# Walrus_Power.net
KiCad netlist of a schematic drawn in Altium Designer
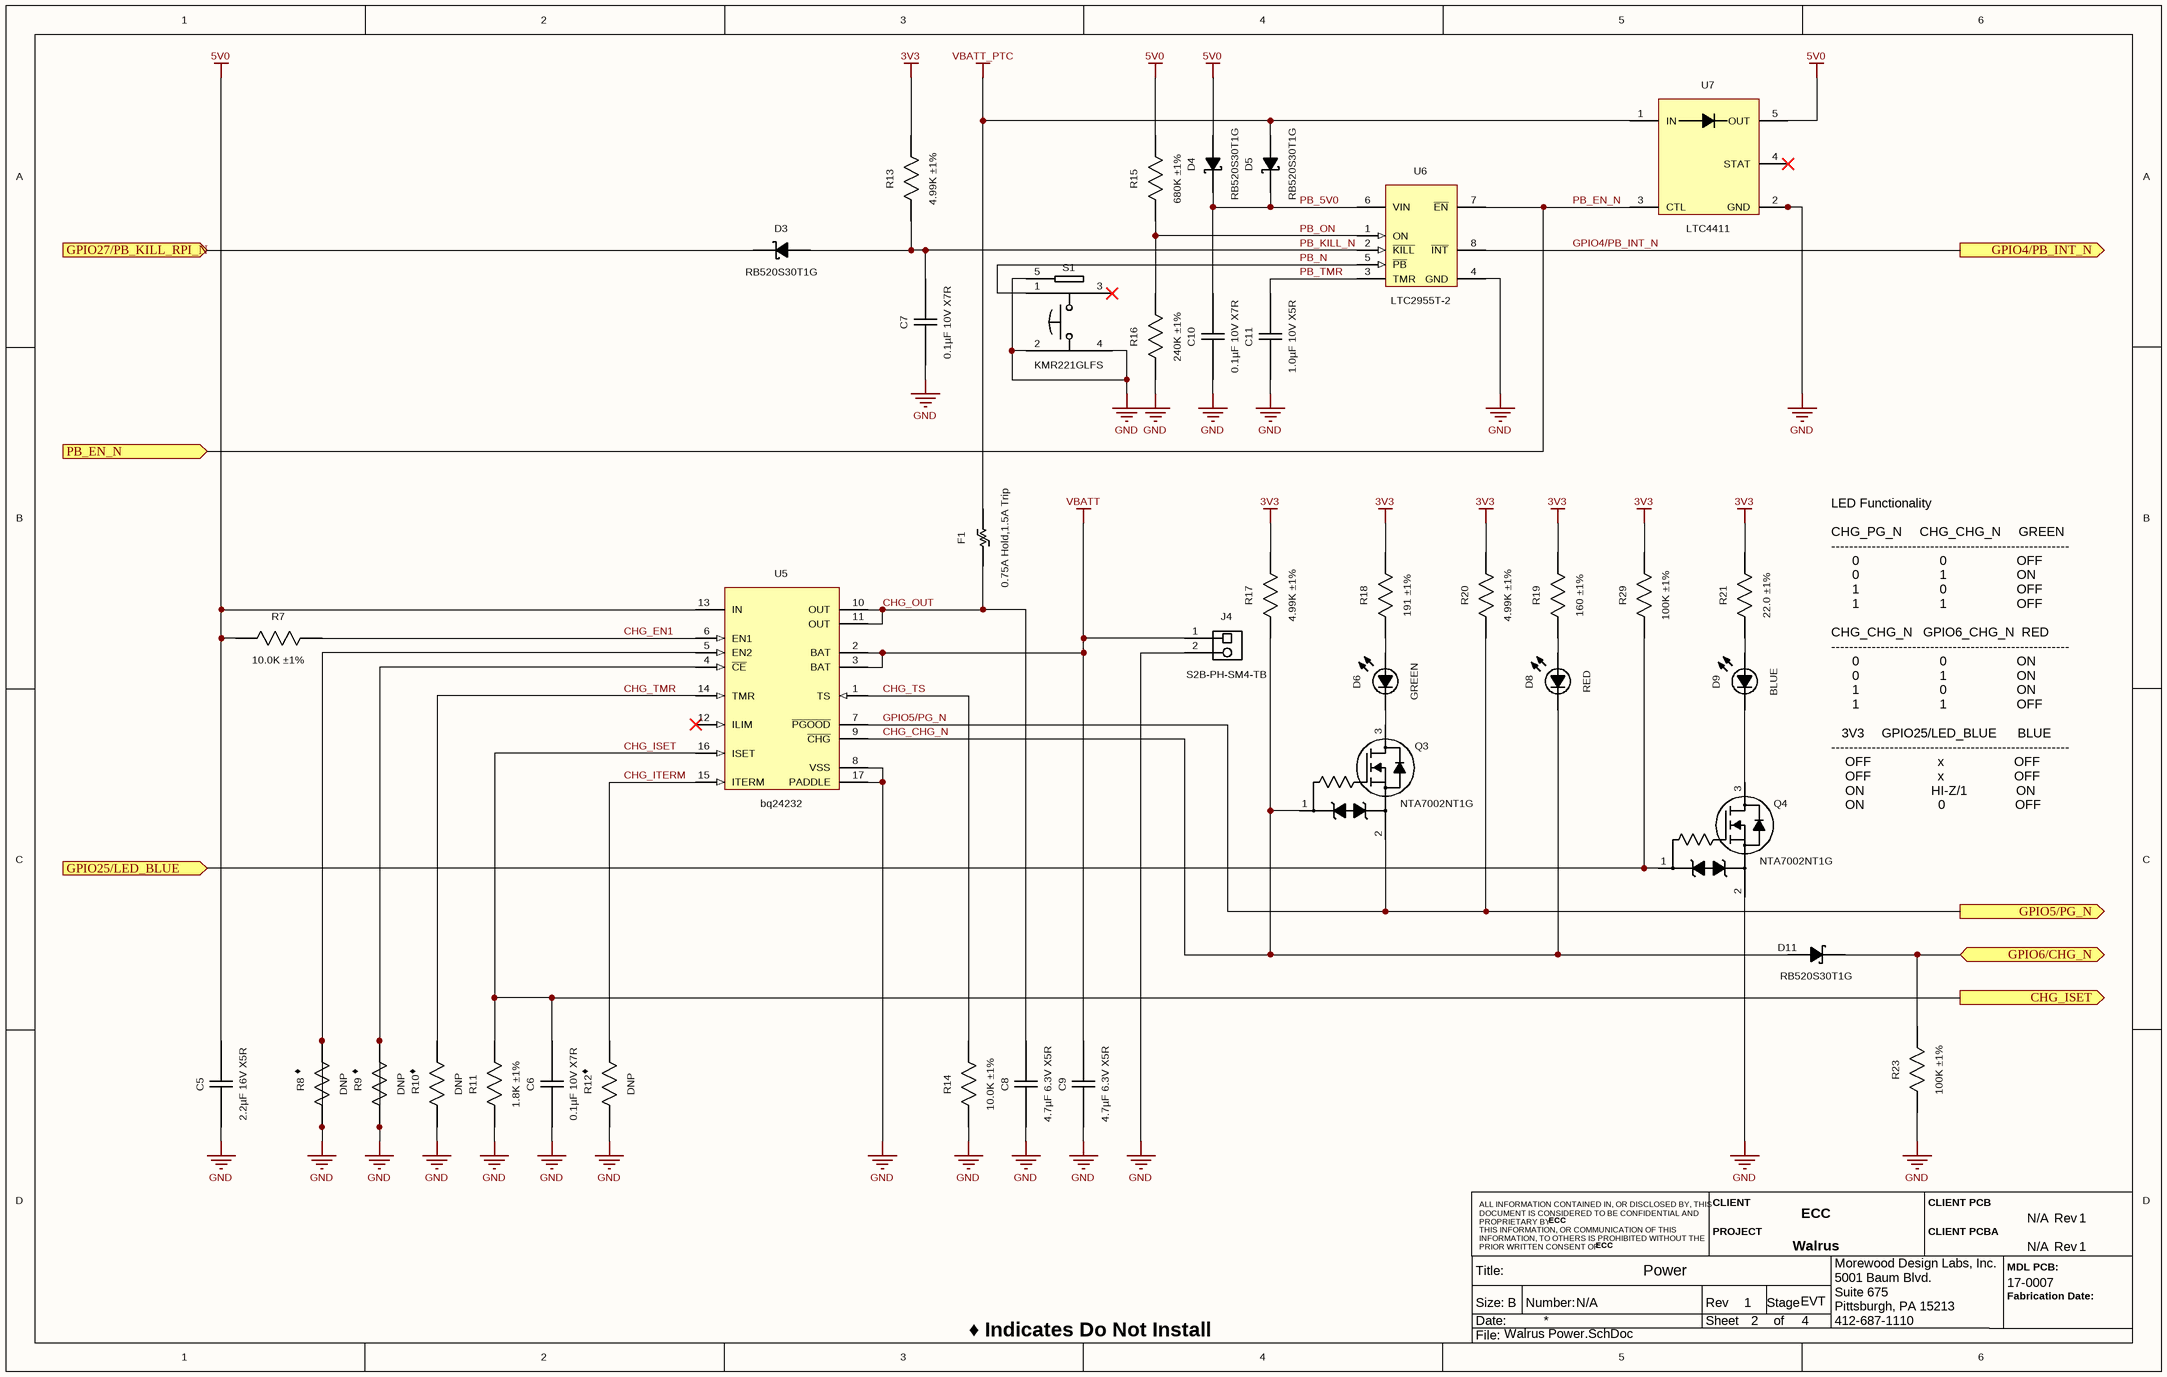
[diagram p0: Walrus Power.SchDoc]

(export (version "E")
  (design (tool "Eeschema 10.0.6"))
  (components
    (comp (ref "C5")
      (value "2.2µF 16V X5R")
      (footprint "CAPC1005X60L(0402)")
      (description "Ceramic Chip Capacitor")
      (fields
        (field (name "MDLPARTNUMBER") "CAP_000166")
        (field (name "TOLERANCE") "±10%")
        (field (name "CREATOR") "R. Casciola")
      )
      (libsource (lib "Morewood Labs") (part "Capacitor 1"))
    )
    (comp (ref "C6")
      (value "0.1µF 10V X7R")
      (footprint "CAPC1005X60L(0402_FLEXTRONICS)")
      (description "Ceramic Chip Capacitor")
      (fields
        (field (name "MDLPARTNUMBER") "CAP_000208")
        (field (name "TOLERANCE") "±10%")
        (field (name "CREATOR") "R. Casciola")
      )
      (libsource (lib "Morewood Labs") (part "Capacitor 1"))
    )
    (comp (ref "C7")
      (value "0.1µF 10V X7R")
      (footprint "CAPC1005X60L(0402_FLEXTRONICS)")
      (description "Ceramic Chip Capacitor")
      (fields
        (field (name "MDLPARTNUMBER") "CAP_000208")
        (field (name "TOLERANCE") "±10%")
        (field (name "CREATOR") "R. Casciola")
      )
      (libsource (lib "Morewood Labs") (part "Capacitor 1"))
    )
    (comp (ref "C8")
      (value "4.7µF 6.3V X5R")
      (footprint "CAPC1005X60L(0402)")
      (description "Ceramic Chip Capacitor")
      (fields
        (field (name "MDLPARTNUMBER") "CAP_000063")
        (field (name "TOLERANCE") "±20%")
        (field (name "CREATOR") "R. Casciola")
      )
      (libsource (lib "Morewood Labs") (part "Capacitor 1"))
    )
    (comp (ref "C9")
      (value "4.7µF 6.3V X5R")
      (footprint "CAPC1005X60L(0402)")
      (description "Ceramic Chip Capacitor")
      (fields
        (field (name "MDLPARTNUMBER") "CAP_000063")
        (field (name "TOLERANCE") "±20%")
        (field (name "CREATOR") "R. Casciola")
      )
      (libsource (lib "Morewood Labs") (part "Capacitor 1"))
    )
    (comp (ref "C10")
      (value "0.1µF 10V X7R")
      (footprint "CAPC1005X60L(0402_FLEXTRONICS)")
      (description "Ceramic Chip Capacitor")
      (fields
        (field (name "MDLPARTNUMBER") "CAP_000208")
        (field (name "TOLERANCE") "±10%")
        (field (name "CREATOR") "R. Casciola")
      )
      (libsource (lib "Morewood Labs") (part "Capacitor 1"))
    )
    (comp (ref "C11")
      (value "1.0µF 10V X5R")
      (footprint "CAPC1005X60L(0402_FLEXTRONICS)")
      (description "Ceramic Chip Capacitor")
      (fields
        (field (name "MDLPARTNUMBER") "CAP_000094")
        (field (name "TOLERANCE") "±10%")
        (field (name "CREATOR") "R. Casciola")
      )
      (libsource (lib "Morewood Labs") (part "Capacitor 1"))
    )
    (comp (ref "D3")
      (value "RB520S30T1G")
      (footprint "SODFL1608X70L(SOD-523)")
      (description "Schottky Barrier Diode")
      (fields (field (name "MDLPARTNUMBER") "DIOD_000001") (field (name "CREATOR") "R. Casciola"))
      (libsource (lib "Morewood Labs") (part "Diode 3"))
    )
    (comp (ref "D4")
      (value "RB520S30T1G")
      (footprint "SODFL1608X70L(SOD-523)")
      (description "Schottky Barrier Diode")
      (fields (field (name "MDLPARTNUMBER") "DIOD_000001") (field (name "CREATOR") "R. Casciola"))
      (libsource (lib "Morewood Labs") (part "Diode 3"))
    )
    (comp (ref "D5")
      (value "RB520S30T1G")
      (footprint "SODFL1608X70L(SOD-523)")
      (description "Schottky Barrier Diode")
      (fields (field (name "MDLPARTNUMBER") "DIOD_000001") (field (name "CREATOR") "R. Casciola"))
      (libsource (lib "Morewood Labs") (part "Diode 3"))
    )
    (comp (ref "D6")
      (value "GREEN")
      (footprint "DIOC1608X90L(0603)_GREEN")
      (description "Surface Mounting Chip LED")
      (fields
        (field (name "MDLPARTNUMBER") "DIOD_000061")
        (field (name "MFG1PARTNUMBER") "LTST-C190KGKT")
        (field (name "CREATOR") "R. Casciola")
      )
      (libsource (lib "Morewood Labs") (part "Diode 5"))
    )
    (comp (ref "D8")
      (value "RED")
      (footprint "DIOC1608X90L(0603)_RED")
      (description "Surface Mounting Chip LED")
      (fields
        (field (name "MDLPARTNUMBER") "DIOD_000068")
        (field (name "MFG1PARTNUMBER") "LTST-C190CKT")
        (field (name "CREATOR") "R. Casciola")
      )
      (libsource (lib "Morewood Labs") (part "Diode 5"))
    )
    (comp (ref "D9")
      (value "BLUE")
      (footprint "DIOC1608X90L(0603)_BLUE")
      (description "Surface Mounting Chip LED")
      (fields
        (field (name "MDLPARTNUMBER") "DIOD_000059")
        (field (name "MFG1PARTNUMBER") "LTST-C190TBKT")
        (field (name "CREATOR") "R. Casciola")
      )
      (libsource (lib "Morewood Labs") (part "Diode 5"))
    )
    (comp (ref "D11")
      (value "RB520S30T1G")
      (footprint "SODFL1608X70L(SOD-523)")
      (description "Schottky Barrier Diode")
      (fields (field (name "MDLPARTNUMBER") "DIOD_000001") (field (name "CREATOR") "R. Casciola"))
      (libsource (lib "Morewood Labs") (part "Diode 3"))
    )
    (comp (ref "F1")
      (value "0.75A Hold,1.5A Trip")
      (footprint "FUSC1608X60N(0603)")
      (description "POLY-FUSE® Resettable PTC, Surface Mount > LoRho Series")
      (fields
        (field (name "MDLPARTNUMBER") "FUSE_000007")
        (field (name "MFG1PARTNUMBER") "0603L075SLYR")
        (field (name "CREATOR") "R. Casciola")
      )
      (libsource (lib "Morewood Labs") (part "PPTC 1"))
    )
    (comp (ref "J4")
      (value "S2B-PH-SM4-TB")
      (footprint "JST_S2B-PH-SM4-TB")
      (description "PH CONNECTOR/2.0MM Pitch Side Entry")
      (fields
        (field (name "MDLPARTNUMBER") "CONN_000190")
        (field (name "MFG1PARTNUMBER") "S2B-PH-SM4-TB,S2B-PH-SM4-TB(LF)(SN)")
        (field (name "CREATOR") "R. Casciola")
        (field (name "MODIFER") "R. Casciola")
      )
      (libsource (lib "Morewood Labs") (part "MHDR1X2"))
    )
    (comp (ref "Q3")
      (value "NTA7002NT1G")
      (footprint "SOT50P160X90-3L(SOT416, SC75)")
      (description "Small Signal MOSFET")
      (fields
        (field (name "MDLPARTNUMBER") "TRAN_000002")
        (field (name "CREATOR") "R. Casciola")
        (field (name "MODIFER") "R. Casciola")
      )
      (libsource (lib "Morewood Labs") (part "MOSFET 2"))
    )
    (comp (ref "Q4")
      (value "NTA7002NT1G")
      (footprint "SOT50P160X90-3L(SOT416, SC75)")
      (description "Small Signal MOSFET")
      (fields
        (field (name "MDLPARTNUMBER") "TRAN_000002")
        (field (name "CREATOR") "R. Casciola")
        (field (name "MODIFER") "R. Casciola")
      )
      (libsource (lib "Morewood Labs") (part "MOSFET 2"))
    )
    (comp (ref "R7")
      (value "10.0K ±1%")
      (footprint "RESC1005X40L(0402)")
      (description "Chip Resistor, Thick Film")
      (fields
        (field (name "MDLPARTNUMBER") "RES_000005")
        (field (name "TOLERANCE") "±1%")
        (field (name "CREATOR") "R. Casciola")
      )
      (libsource (lib "Morewood Labs") (part "Resistor 1"))
    )
    (comp (ref "R8")
      (value "DNP")
      (footprint "RESC1005X40L(0402)_DNP")
      (description "Chip Resistor, Thick Film")
      (fields
        (field (name "DNI") "♦")
        (field (name "MDLPARTNUMBER") "RES_000064")
        (field (name "CREATOR") "R. Casciola")
      )
      (libsource (lib "Morewood Labs") (part "Resistor 2"))
    )
    (comp (ref "R9")
      (value "DNP")
      (footprint "RESC1005X40L(0402)_DNP")
      (description "Chip Resistor, Thick Film")
      (fields
        (field (name "DNI") "♦")
        (field (name "MDLPARTNUMBER") "RES_000064")
        (field (name "CREATOR") "R. Casciola")
      )
      (libsource (lib "Morewood Labs") (part "Resistor 2"))
    )
    (comp (ref "R10")
      (value "DNP")
      (footprint "RESC1005X40L(0402)_DNP")
      (description "Chip Resistor, Thick Film")
      (fields
        (field (name "DNI") "♦")
        (field (name "MDLPARTNUMBER") "RES_000064")
        (field (name "CREATOR") "R. Casciola")
      )
      (libsource (lib "Morewood Labs") (part "Resistor 2"))
    )
    (comp (ref "R11")
      (value "1.8K ±1%")
      (footprint "RESC1005X40L(0402)")
      (description "Chip Resistor, Thick Film")
      (fields
        (field (name "MDLPARTNUMBER") "RES_000288")
        (field (name "TOLERANCE") "±1%")
        (field (name "CREATOR") "R. Casciola")
      )
      (libsource (lib "Morewood Labs") (part "Resistor 1"))
    )
    (comp (ref "R12")
      (value "DNP")
      (footprint "RESC1005X40L(0402)_DNP")
      (description "Chip Resistor, Thick Film")
      (fields
        (field (name "DNI") "♦")
        (field (name "MDLPARTNUMBER") "RES_000064")
        (field (name "CREATOR") "R. Casciola")
      )
      (libsource (lib "Morewood Labs") (part "Resistor 2"))
    )
    (comp (ref "R13")
      (value "4.99K ±1%")
      (footprint "RESC1005X40L(0402)")
      (description "Chip Resistor, Thick Film")
      (fields
        (field (name "MDLPARTNUMBER") "RES_000003")
        (field (name "TOLERANCE") "±1%")
        (field (name "CREATOR") "R. Casciola")
      )
      (libsource (lib "Morewood Labs") (part "Resistor 1"))
    )
    (comp (ref "R14")
      (value "10.0K ±1%")
      (footprint "RESC1005X40L(0402)")
      (description "Chip Resistor, Thick Film")
      (fields
        (field (name "MDLPARTNUMBER") "RES_000005")
        (field (name "TOLERANCE") "±1%")
        (field (name "CREATOR") "R. Casciola")
      )
      (libsource (lib "Morewood Labs") (part "Resistor 1"))
    )
    (comp (ref "R15")
      (value "680K ±1%")
      (footprint "RESC1005X40L(0402)")
      (description "Chip Resistor, Thick Film")
      (fields
        (field (name "MDLPARTNUMBER") "RES_000103")
        (field (name "TOLERANCE") "±1%")
        (field (name "CREATOR") "R. Casciola")
      )
      (libsource (lib "Morewood Labs") (part "Resistor 1"))
    )
    (comp (ref "R16")
      (value "240K ±1%")
      (footprint "RESC1005X40L(0402)")
      (description "Chip Resistor, Thick Film")
      (fields
        (field (name "MDLPARTNUMBER") "RES_000165")
        (field (name "TOLERANCE") "±1%")
        (field (name "CREATOR") "R. Casciola")
      )
      (libsource (lib "Morewood Labs") (part "Resistor 1"))
    )
    (comp (ref "R17")
      (value "4.99K ±1%")
      (footprint "RESC1005X40L(0402)")
      (description "Chip Resistor, Thick Film")
      (fields
        (field (name "MDLPARTNUMBER") "RES_000003")
        (field (name "TOLERANCE") "±1%")
        (field (name "CREATOR") "R. Casciola")
      )
      (libsource (lib "Morewood Labs") (part "Resistor 1"))
    )
    (comp (ref "R18")
      (value "191 ±1%")
      (footprint "RESC1005X40L(0402)")
      (description "Chip Resistor, Thick Film")
      (fields
        (field (name "MDLPARTNUMBER") "RES_000287")
        (field (name "TOLERANCE") "±1%")
        (field (name "CREATOR") "R. Casciola")
      )
      (libsource (lib "Morewood Labs") (part "Resistor 1"))
    )
    (comp (ref "R19")
      (value "160 ±1%")
      (footprint "RESC1005X40L(0402)")
      (description "Chip Resistor, Thick Film")
      (fields
        (field (name "MDLPARTNUMBER") "RES_000286")
        (field (name "TOLERANCE") "±1%")
        (field (name "CREATOR") "R. Casciola")
      )
      (libsource (lib "Morewood Labs") (part "Resistor 1"))
    )
    (comp (ref "R20")
      (value "4.99K ±1%")
      (footprint "RESC1005X40L(0402)")
      (description "Chip Resistor, Thick Film")
      (fields
        (field (name "MDLPARTNUMBER") "RES_000003")
        (field (name "TOLERANCE") "±1%")
        (field (name "CREATOR") "R. Casciola")
      )
      (libsource (lib "Morewood Labs") (part "Resistor 1"))
    )
    (comp (ref "R21")
      (value "22.0 ±1%")
      (footprint "RESC1005X40L(0402)")
      (description "Chip Resistor, Thick Film")
      (fields
        (field (name "MDLPARTNUMBER") "RES_000158")
        (field (name "TOLERANCE") "±1%")
        (field (name "CREATOR") "R. Casciola")
      )
      (libsource (lib "Morewood Labs") (part "Resistor 1"))
    )
    (comp (ref "R23")
      (value "100K ±1%")
      (footprint "RESC1005X40L(0402)")
      (description "Chip Resistor, Thick Film")
      (fields
        (field (name "MDLPARTNUMBER") "RES_000067")
        (field (name "TOLERANCE") "±1%")
        (field (name "CREATOR") "R. Casciola")
      )
      (libsource (lib "Morewood Labs") (part "Resistor 1"))
    )
    (comp (ref "R29")
      (value "100K ±1%")
      (footprint "RESC1005X40L(0402)")
      (description "Chip Resistor, Thick Film")
      (fields
        (field (name "MDLPARTNUMBER") "RES_000067")
        (field (name "TOLERANCE") "±1%")
        (field (name "CREATOR") "R. Casciola")
      )
      (libsource (lib "Morewood Labs") (part "Resistor 1"))
    )
    (comp (ref "S1")
      (value "KMR221GLFS")
      (footprint "KMR221GLFS")
      (description "KMR 2 Series Microminiature SMT Top Actuated")
      (fields
        (field (name "MDLPARTNUMBER") "SWCH_000001")
        (field (name "CREATOR") "R. Casciola")
        (field (name "MODIFER") "R. Casciola")
      )
      (libsource (lib "Morewood Labs") (part "Switch 1"))
    )
    (comp (ref "U5")
      (value "bq24232")
      (footprint "QFN50P300X300X100-17N(bq24232)")
      (description "USB-FRIENDLY LITHIUM-ION BATTERY CHARGER AND POWER-PATH MANAGEMENT IC")
      (fields
        (field (name "MDLPARTNUMBER") "IC_000195")
        (field (name "MFG1PARTNUMBER") "BQ24232RGTR,BQ24232RGTT")
        (field (name "CREATOR") "R. Casciola")
        (field (name "MODIFER") "R. Casciola")
      )
      (libsource (lib "Morewood Labs") (part "bq24232RGT"))
    )
    (comp (ref "U6")
      (value "LTC2955T-2")
      (footprint "SOT65P280X100-8L(TSOT23-8)")
      (description "Pushbutton On/Off Controller with Automatic Turn-On")
      (fields
        (field (name "MDLPARTNUMBER") "IC_000294")
        (field (name "MFG1PARTNUMBER") "LTC2955CTS8-2#PBF,LTC2955CTS8-2#TRMPBF,LTC2955CTS8-2#TRPBF")
        (field (name "CREATOR") "R. Casciola")
        (field (name "MODIFER") "R. Casciola")
      )
      (libsource (lib "Morewood Labs") (part "LTC2955T-2"))
    )
    (comp (ref "U7")
      (value "LTC4411")
      (footprint "SOT95P280X100-5L(TSOT23 -5)")
      (description "2.6A Low Loss Ideal Diode in ThinSOT")
      (fields
        (field (name "MDLPARTNUMBER") "IC_000293")
        (field (name "MFG1PARTNUMBER") "LTC4411ES5,LTC4411ES5#TRMPBF,LTC4411ES5#TRPBF")
        (field (name "CREATOR") "R. Casciola")
        (field (name "MODIFER") "R. Casciola")
      )
      (libsource (lib "Morewood Labs") (part "LTC4411"))
    )
  )
  (nets
    (net (code "1") (name "/CHG_CHG_N") (class "Default")
      (node (ref "D11") (pin "2") (pinfunction "A_2") (pintype "passive"))
      (node (ref "D8") (pin "1") (pinfunction "K_1") (pintype "passive"))
      (node (ref "Q3") (pin "1") (pinfunction "G_1") (pintype "passive"))
      (node (ref "R17") (pin "1") (pinfunction "1_1") (pintype "passive"))
      (node (ref "U5") (pin "9") (pinfunction "~{CHG}_9") (pintype "open_collector"))
    )
    (net (code "2") (name "/CHG_EN1") (class "Default")
      (node (ref "R7") (pin "2") (pinfunction "2_2") (pintype "passive"))
      (node (ref "U5") (pin "6") (pinfunction "EN1_6") (pintype "input"))
    )
    (net (code "3") (name "/CHG_ISET") (class "Default")
      (node (ref "C6") (pin "2") (pinfunction "2_2") (pintype "passive"))
      (node (ref "R11") (pin "2") (pinfunction "2_2") (pintype "passive"))
      (node (ref "U5") (pin "16") (pinfunction "ISET_16") (pintype "input"))
    )
    (net (code "4") (name "/CHG_ITERM") (class "Default")
      (node (ref "R12") (pin "2") (pinfunction "2_2") (pintype "passive"))
      (node (ref "U5") (pin "15") (pinfunction "ITERM_15") (pintype "input"))
    )
    (net (code "5") (name "/CHG_OUT") (class "Default")
      (node (ref "C8") (pin "2") (pinfunction "2_2") (pintype "passive"))
      (node (ref "F1") (pin "1") (pinfunction "1_1") (pintype "passive"))
      (node (ref "U5") (pin "10") (pinfunction "OUT_10") (pintype "power_in"))
      (node (ref "U5") (pin "11") (pinfunction "OUT_11") (pintype "power_in"))
    )
    (net (code "6") (name "/CHG_TMR") (class "Default")
      (node (ref "R10") (pin "2") (pinfunction "2_2") (pintype "passive"))
      (node (ref "U5") (pin "14") (pinfunction "TMR_14") (pintype "input"))
    )
    (net (code "7") (name "/CHG_TS") (class "Default")
      (node (ref "R14") (pin "2") (pinfunction "2_2") (pintype "passive"))
      (node (ref "U5") (pin "1") (pinfunction "TS_1") (pintype "input"))
    )
    (net (code "8") (name "/GPIO4{slash}PB_INT_N") (class "Default")
      (node (ref "U6") (pin "8") (pinfunction "~{INT}_8") (pintype "open_collector"))
    )
    (net (code "9") (name "/GPIO5{slash}PG_N") (class "Default")
      (node (ref "Q3") (pin "2") (pinfunction "S_2") (pintype "passive"))
      (node (ref "R20") (pin "1") (pinfunction "1_1") (pintype "passive"))
      (node (ref "U5") (pin "7") (pinfunction "~{PGOOD}_7") (pintype "open_collector"))
    )
    (net (code "10") (name "/GPIO6{slash}CHG_N") (class "Default")
      (node (ref "D11") (pin "1") (pinfunction "K_1") (pintype "passive"))
      (node (ref "R23") (pin "2") (pinfunction "2_2") (pintype "passive"))
    )
    (net (code "11") (name "/GPIO25{slash}LED_BLUE") (class "Default")
      (node (ref "Q4") (pin "1") (pinfunction "G_1") (pintype "passive"))
      (node (ref "R29") (pin "1") (pinfunction "1_1") (pintype "passive"))
    )
    (net (code "12") (name "/GPIO27{slash}PB_KILL_RPI_N") (class "Default")
      (node (ref "D3") (pin "1") (pinfunction "K_1") (pintype "passive"))
    )
    (net (code "13") (name "/PB_5V0") (class "Default")
      (node (ref "C10") (pin "2") (pinfunction "2_2") (pintype "passive"))
      (node (ref "D4") (pin "1") (pinfunction "K_1") (pintype "passive"))
      (node (ref "D5") (pin "1") (pinfunction "K_1") (pintype "passive"))
      (node (ref "U6") (pin "6") (pinfunction "VIN_6") (pintype "power_in"))
    )
    (net (code "14") (name "/PB_EN_N") (class "Default")
      (node (ref "U6") (pin "7") (pinfunction "~{EN}_7") (pintype "open_collector"))
      (node (ref "U7") (pin "3") (pinfunction "CTL_3") (pintype "passive"))
    )
    (net (code "15") (name "/PB_KILL_N") (class "Default")
      (node (ref "C7") (pin "2") (pinfunction "2_2") (pintype "passive"))
      (node (ref "D3") (pin "2") (pinfunction "A_2") (pintype "passive"))
      (node (ref "R13") (pin "1") (pinfunction "1_1") (pintype "passive"))
      (node (ref "U6") (pin "2") (pinfunction "~{KILL}_2") (pintype "input"))
    )
    (net (code "16") (name "/PB_N") (class "Default")
      (node (ref "S1") (pin "1") (pinfunction "A_1") (pintype "passive"))
      (node (ref "U6") (pin "5") (pinfunction "~{PB}_5") (pintype "input"))
    )
    (net (code "17") (name "/PB_ON") (class "Default")
      (node (ref "R15") (pin "1") (pinfunction "1_1") (pintype "passive"))
      (node (ref "R16") (pin "2") (pinfunction "2_2") (pintype "passive"))
      (node (ref "U6") (pin "1") (pinfunction "ON_1") (pintype "input"))
    )
    (net (code "18") (name "/PB_TMR") (class "Default")
      (node (ref "C11") (pin "2") (pinfunction "2_2") (pintype "passive"))
      (node (ref "U6") (pin "3") (pinfunction "TMR_3") (pintype "passive"))
    )
    (net (code "19") (name "3V3") (class "Default")
      (node (ref "R13") (pin "2") (pinfunction "2_2") (pintype "passive"))
      (node (ref "R17") (pin "2") (pinfunction "2_2") (pintype "passive"))
      (node (ref "R18") (pin "2") (pinfunction "2_2") (pintype "passive"))
      (node (ref "R19") (pin "2") (pinfunction "2_2") (pintype "passive"))
      (node (ref "R20") (pin "2") (pinfunction "2_2") (pintype "passive"))
      (node (ref "R21") (pin "2") (pinfunction "2_2") (pintype "passive"))
      (node (ref "R29") (pin "2") (pinfunction "2_2") (pintype "passive"))
    )
    (net (code "20") (name "5V0") (class "Default")
      (node (ref "C5") (pin "2") (pinfunction "2_2") (pintype "passive"))
      (node (ref "D4") (pin "2") (pinfunction "A_2") (pintype "passive"))
      (node (ref "R15") (pin "2") (pinfunction "2_2") (pintype "passive"))
      (node (ref "R7") (pin "1") (pinfunction "1_1") (pintype "passive"))
      (node (ref "U5") (pin "13") (pinfunction "IN_13") (pintype "power_in"))
      (node (ref "U7") (pin "5") (pinfunction "OUT_5") (pintype "power_in"))
    )
    (net (code "21") (name "GND") (class "Default")
      (node (ref "C10") (pin "1") (pinfunction "1_1") (pintype "passive"))
      (node (ref "C11") (pin "1") (pinfunction "1_1") (pintype "passive"))
      (node (ref "C5") (pin "1") (pinfunction "1_1") (pintype "passive"))
      (node (ref "C6") (pin "1") (pinfunction "1_1") (pintype "passive"))
      (node (ref "C7") (pin "1") (pinfunction "1_1") (pintype "passive"))
      (node (ref "C8") (pin "1") (pinfunction "1_1") (pintype "passive"))
      (node (ref "C9") (pin "1") (pinfunction "1_1") (pintype "passive"))
      (node (ref "J4") (pin "2") (pinfunction "2_2") (pintype "passive"))
      (node (ref "Q4") (pin "2") (pinfunction "S_2") (pintype "passive"))
      (node (ref "R10") (pin "1") (pinfunction "1_1") (pintype "passive"))
      (node (ref "R11") (pin "1") (pinfunction "1_1") (pintype "passive"))
      (node (ref "R12") (pin "1") (pinfunction "1_1") (pintype "passive"))
      (node (ref "R14") (pin "1") (pinfunction "1_1") (pintype "passive"))
      (node (ref "R16") (pin "1") (pinfunction "1_1") (pintype "passive"))
      (node (ref "R23") (pin "1") (pinfunction "1_1") (pintype "passive"))
      (node (ref "R8") (pin "1") (pinfunction "1_1") (pintype "passive"))
      (node (ref "R8") (pin "2") (pinfunction "2_2") (pintype "passive"))
      (node (ref "R9") (pin "1") (pinfunction "1_1") (pintype "passive"))
      (node (ref "R9") (pin "2") (pinfunction "2_2") (pintype "passive"))
      (node (ref "S1") (pin "2") (pinfunction "B_2") (pintype "passive"))
      (node (ref "S1") (pin "4") (pinfunction "B'_4") (pintype "passive"))
      (node (ref "S1") (pin "5") (pinfunction "BODY_5") (pintype "passive"))
      (node (ref "U5") (pin "17") (pinfunction "PADDLE_17") (pintype "power_in"))
      (node (ref "U5") (pin "4") (pinfunction "~{CE}_4") (pintype "input"))
      (node (ref "U5") (pin "5") (pinfunction "EN2_5") (pintype "input"))
      (node (ref "U5") (pin "8") (pinfunction "VSS_8") (pintype "power_in"))
      (node (ref "U6") (pin "4") (pinfunction "GND_4") (pintype "power_in"))
      (node (ref "U7") (pin "2") (pinfunction "GND_2") (pintype "power_in"))
    )
    (net (code "22") (name "Net-(D6-A)") (class "Default")
      (node (ref "D6") (pin "2") (pinfunction "A_2") (pintype "passive"))
      (node (ref "R18") (pin "1") (pinfunction "1_1") (pintype "passive"))
    )
    (net (code "23") (name "Net-(D6-K)") (class "Default")
      (node (ref "D6") (pin "1") (pinfunction "K_1") (pintype "passive"))
      (node (ref "Q3") (pin "3") (pinfunction "D_3") (pintype "passive"))
    )
    (net (code "24") (name "Net-(D8-A)") (class "Default")
      (node (ref "D8") (pin "2") (pinfunction "A_2") (pintype "passive"))
      (node (ref "R19") (pin "1") (pinfunction "1_1") (pintype "passive"))
    )
    (net (code "25") (name "Net-(D9-A)") (class "Default")
      (node (ref "D9") (pin "2") (pinfunction "A_2") (pintype "passive"))
      (node (ref "R21") (pin "1") (pinfunction "1_1") (pintype "passive"))
    )
    (net (code "26") (name "Net-(D9-K)") (class "Default")
      (node (ref "D9") (pin "1") (pinfunction "K_1") (pintype "passive"))
      (node (ref "Q4") (pin "3") (pinfunction "D_3") (pintype "passive"))
    )
    (net (code "27") (name "VBATT") (class "Default")
      (node (ref "C9") (pin "2") (pinfunction "2_2") (pintype "passive"))
      (node (ref "J4") (pin "1") (pinfunction "1_1") (pintype "passive"))
      (node (ref "U5") (pin "2") (pinfunction "BAT_2") (pintype "power_in"))
      (node (ref "U5") (pin "3") (pinfunction "BAT_3") (pintype "power_in"))
    )
    (net (code "28") (name "VBATT_PTC") (class "Default")
      (node (ref "D5") (pin "2") (pinfunction "A_2") (pintype "passive"))
      (node (ref "F1") (pin "2") (pinfunction "2_2") (pintype "passive"))
      (node (ref "U7") (pin "1") (pinfunction "IN_1") (pintype "power_in"))
    )
    (net (code "29") (name "unconnected-(S1-A'-Pad3)") (class "Default")
      (node (ref "S1") (pin "3") (pinfunction "A'_3") (pintype "passive+no_connect"))
    )
    (net (code "30") (name "unconnected-(U5-ILIM-Pad12)") (class "Default")
      (node (ref "U5") (pin "12") (pinfunction "ILIM_12") (pintype "input+no_connect"))
    )
    (net (code "31") (name "unconnected-(U7-STAT-Pad4)") (class "Default")
      (node (ref "U7") (pin "4") (pinfunction "STAT_4") (pintype "open_collector+no_connect"))
    )
  )
)
